# macse.net
KiCad netlist of a schematic drawn in EAGLE
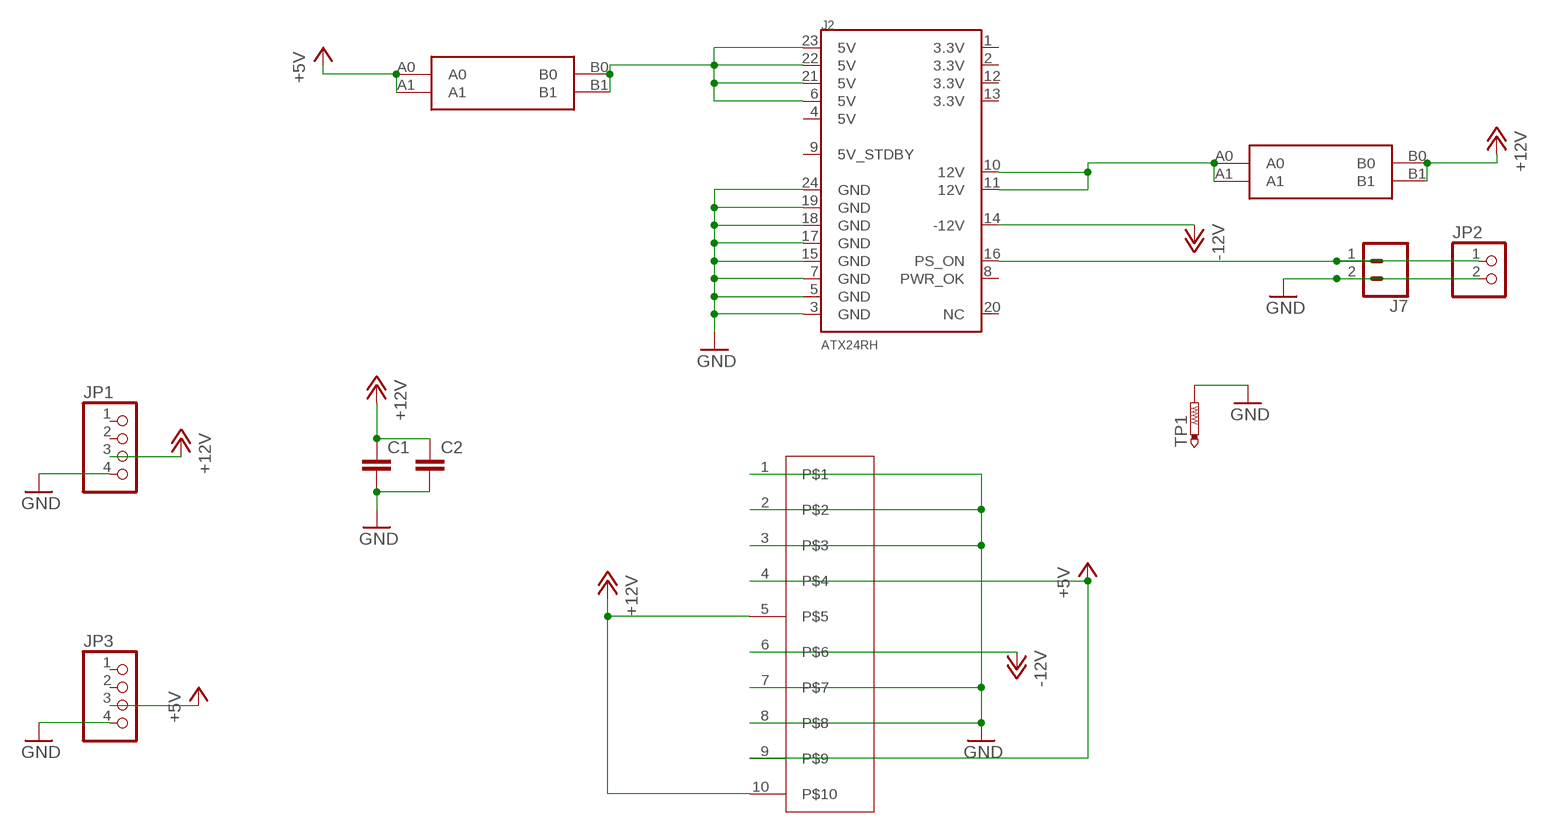
[diagram p0: schematic, sheet 1]

(export (version "E")
  (design (tool "Eeschema 10.0.6"))
  (components
    (comp (ref "C1")
      (value "C5/2.5")
      (footprint "eagle-import:C5B2.5")
      (libsource (lib "eagle-import") (part "C5/2.5"))
    )
    (comp (ref "C2")
      (value "C5/2.5")
      (footprint "eagle-import:C5B2.5")
      (libsource (lib "eagle-import") (part "C5/2.5"))
    )
    (comp (ref "J2")
      (value "ATX24RH")
      (footprint "eagle-import:ATX24_RIGHT_ANGLE")
      (libsource (lib "eagle-import") (part "ATX24RH"))
    )
    (comp (ref "J7")
      (value "CONN_023.5MM-NO_SILK")
      (footprint "eagle-import:SCREWTERMINAL-3.5MM-2-NS")
      (libsource (lib "eagle-import") (part "CONN_023.5MM-NO_SILK"))
    )
    (comp (ref "JP1")
      (value "PINHD-1X4")
      (footprint "eagle-import:1X04")
      (libsource (lib "eagle-import") (part "PINHD-1X4"))
    )
    (comp (ref "JP2")
      (value "PINHD-1X2")
      (footprint "eagle-import:1X02")
      (libsource (lib "eagle-import") (part "PINHD-1X2"))
    )
    (comp (ref "JP3")
      (value "PINHD-1X4")
      (footprint "eagle-import:1X04")
      (libsource (lib "eagle-import") (part "PINHD-1X4"))
    )
    (comp (ref "TP1")
      (value "PTR1PAD1-20Y")
      (footprint "eagle-import:P1-20Y")
      (libsource (lib "eagle-import") (part "PTR1PAD1-20Y"))
    )
    (comp (ref "U$1")
      (value "MACSE")
      (footprint "eagle-import:MACSE_10P_STRAIGHT")
      (libsource (lib "eagle-import") (part "MACSE"))
    )
    (comp (ref "U$2")
      (value "CAR_FUSE_HOLDER3IN1")
      (footprint "eagle-import:FUSE_HOLDER_3IN1")
      (libsource (lib "eagle-import") (part "CAR_FUSE_HOLDER3IN1"))
    )
    (comp (ref "U$8")
      (value "CAR_FUSE_HOLDER3IN1")
      (footprint "eagle-import:FUSE_HOLDER_3IN1")
      (libsource (lib "eagle-import") (part "CAR_FUSE_HOLDER3IN1"))
    )
  )
  (nets
    (net (code "1") (name "+5V") (class "Default")
      (node (ref "JP3") (pin "3") (pinfunction "3_3") (pintype "passive"))
      (node (ref "U$1") (pin "4") (pinfunction "P$4_4") (pintype "bidirectional"))
      (node (ref "U$1") (pin "9") (pinfunction "P$9_9") (pintype "bidirectional"))
      (node (ref "U$8") (pin "A0") (pinfunction "A0_A0") (pintype "bidirectional"))
      (node (ref "U$8") (pin "A1") (pinfunction "A1_A1") (pintype "bidirectional"))
    )
    (net (code "2") (name "+12V") (class "Default")
      (node (ref "C1") (pin "1") (pinfunction "1_1") (pintype "passive"))
      (node (ref "C2") (pin "1") (pinfunction "1_1") (pintype "passive"))
      (node (ref "JP1") (pin "3") (pinfunction "3_3") (pintype "passive"))
      (node (ref "U$1") (pin "10") (pinfunction "P$10_10") (pintype "bidirectional"))
      (node (ref "U$1") (pin "5") (pinfunction "P$5_5") (pintype "bidirectional"))
      (node (ref "U$2") (pin "B0") (pinfunction "B0_B0") (pintype "bidirectional"))
      (node (ref "U$2") (pin "B1") (pinfunction "B1_B1") (pintype "bidirectional"))
    )
    (net (code "3") (name "-12V") (class "Default")
      (node (ref "J2") (pin "14") (pinfunction "-12V_14") (pintype "bidirectional"))
      (node (ref "U$1") (pin "6") (pinfunction "P$6_6") (pintype "bidirectional"))
    )
    (net (code "4") (name "GND") (class "Default")
      (node (ref "C1") (pin "2") (pinfunction "2_2") (pintype "passive"))
      (node (ref "C2") (pin "2") (pinfunction "2_2") (pintype "passive"))
      (node (ref "J2") (pin "15") (pinfunction "GND_15") (pintype "bidirectional"))
      (node (ref "J2") (pin "17") (pinfunction "GND_17") (pintype "bidirectional"))
      (node (ref "J2") (pin "18") (pinfunction "GND_18") (pintype "bidirectional"))
      (node (ref "J2") (pin "19") (pinfunction "GND_19") (pintype "bidirectional"))
      (node (ref "J2") (pin "24") (pinfunction "GND_24") (pintype "bidirectional"))
      (node (ref "J2") (pin "3") (pinfunction "GND_3") (pintype "bidirectional"))
      (node (ref "J2") (pin "5") (pinfunction "GND_5") (pintype "bidirectional"))
      (node (ref "J2") (pin "7") (pinfunction "GND_7") (pintype "bidirectional"))
      (node (ref "J7") (pin "2") (pinfunction "2_2") (pintype "passive"))
      (node (ref "JP1") (pin "4") (pinfunction "4_4") (pintype "passive"))
      (node (ref "JP2") (pin "2") (pinfunction "2_2") (pintype "passive"))
      (node (ref "JP3") (pin "4") (pinfunction "4_4") (pintype "passive"))
      (node (ref "TP1") (pin "TP") (pinfunction "TP_TP") (pintype "input"))
      (node (ref "U$1") (pin "1") (pinfunction "P$1_1") (pintype "bidirectional"))
      (node (ref "U$1") (pin "2") (pinfunction "P$2_2") (pintype "bidirectional"))
      (node (ref "U$1") (pin "3") (pinfunction "P$3_3") (pintype "bidirectional"))
      (node (ref "U$1") (pin "7") (pinfunction "P$7_7") (pintype "bidirectional"))
      (node (ref "U$1") (pin "8") (pinfunction "P$8_8") (pintype "bidirectional"))
    )
    (net (code "5") (name "Net-(J2-5V-Pad21)") (class "Default")
      (node (ref "J2") (pin "21") (pinfunction "5V_21") (pintype "bidirectional"))
      (node (ref "J2") (pin "22") (pinfunction "5V_22") (pintype "bidirectional"))
      (node (ref "J2") (pin "23") (pinfunction "5V_23") (pintype "bidirectional"))
      (node (ref "J2") (pin "6") (pinfunction "5V_6") (pintype "bidirectional"))
      (node (ref "U$8") (pin "B0") (pinfunction "B0_B0") (pintype "bidirectional"))
      (node (ref "U$8") (pin "B1") (pinfunction "B1_B1") (pintype "bidirectional"))
    )
    (net (code "6") (name "Net-(J2-12V-Pad10)") (class "Default")
      (node (ref "J2") (pin "10") (pinfunction "12V_10") (pintype "bidirectional"))
      (node (ref "J2") (pin "11") (pinfunction "12V_11") (pintype "bidirectional"))
      (node (ref "U$2") (pin "A0") (pinfunction "A0_A0") (pintype "bidirectional"))
      (node (ref "U$2") (pin "A1") (pinfunction "A1_A1") (pintype "bidirectional"))
    )
    (net (code "7") (name "Net-(J2-PS_ON)") (class "Default")
      (node (ref "J2") (pin "16") (pinfunction "PS_ON_16") (pintype "bidirectional"))
      (node (ref "J7") (pin "1") (pinfunction "1_1") (pintype "passive"))
      (node (ref "JP2") (pin "1") (pinfunction "1_1") (pintype "passive"))
    )
    (net (code "8") (name "unconnected-(J2-3.3V-Pad1)") (class "Default")
      (node (ref "J2") (pin "1") (pinfunction "3.3V_1") (pintype "bidirectional"))
    )
    (net (code "9") (name "unconnected-(J2-3.3V-Pad2)") (class "Default")
      (node (ref "J2") (pin "2") (pinfunction "3.3V_2") (pintype "bidirectional"))
    )
    (net (code "10") (name "unconnected-(J2-3.3V-Pad12)") (class "Default")
      (node (ref "J2") (pin "12") (pinfunction "3.3V_12") (pintype "bidirectional"))
    )
    (net (code "11") (name "unconnected-(J2-3.3V-Pad13)") (class "Default")
      (node (ref "J2") (pin "13") (pinfunction "3.3V_13") (pintype "bidirectional"))
    )
    (net (code "12") (name "unconnected-(J2-5V-Pad4)") (class "Default")
      (node (ref "J2") (pin "4") (pinfunction "5V_4") (pintype "bidirectional"))
    )
    (net (code "13") (name "unconnected-(J2-5V_STDBY-Pad9)") (class "Default")
      (node (ref "J2") (pin "9") (pinfunction "5V_STDBY_9") (pintype "bidirectional"))
    )
    (net (code "14") (name "unconnected-(J2-NC-Pad20)") (class "Default")
      (node (ref "J2") (pin "20") (pinfunction "NC_20") (pintype "bidirectional"))
    )
    (net (code "15") (name "unconnected-(J2-PWR_OK-Pad8)") (class "Default")
      (node (ref "J2") (pin "8") (pinfunction "PWR_OK_8") (pintype "bidirectional"))
    )
    (net (code "16") (name "unconnected-(JP1-Pad1)") (class "Default")
      (node (ref "JP1") (pin "1") (pinfunction "1_1") (pintype "passive"))
    )
    (net (code "17") (name "unconnected-(JP1-Pad2)") (class "Default")
      (node (ref "JP1") (pin "2") (pinfunction "2_2") (pintype "passive"))
    )
    (net (code "18") (name "unconnected-(JP3-Pad1)") (class "Default")
      (node (ref "JP3") (pin "1") (pinfunction "1_1") (pintype "passive"))
    )
    (net (code "19") (name "unconnected-(JP3-Pad2)") (class "Default")
      (node (ref "JP3") (pin "2") (pinfunction "2_2") (pintype "passive"))
    )
  )
)
